# Water_Schematic2_1.net
KiCad netlist of a schematic drawn in EAGLE
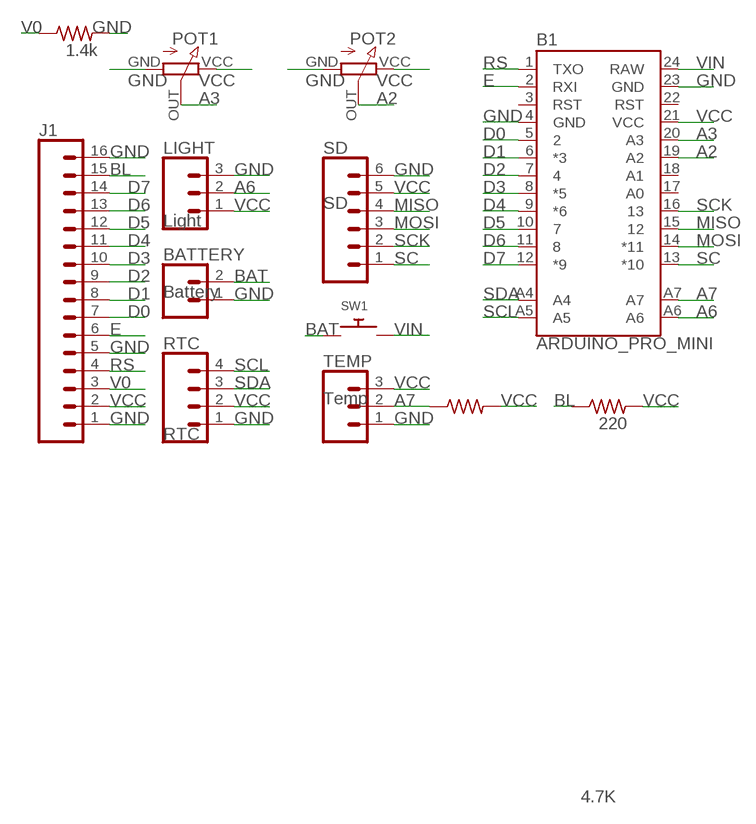
[diagram p0: schematic, sheet 1]

(export (version "E")
  (design (tool "Eeschema 10.0.6"))
  (components
    (comp (ref "B1")
      (value "ARDUINO_PRO_MINI")
      (footprint "eagle-import:ARDUINO_PRO_MINI")
      (libsource (lib "eagle-import") (part "ARDUINO_PRO_MINI"))
    )
    (comp (ref "BATTERY")
      (value "Battery")
      (footprint "eagle-import:MOLEX-1X2")
      (libsource (lib "eagle-import") (part "CONN_02POLAR"))
    )
    (comp (ref "J1")
      (value "CONN_16")
      (footprint "eagle-import:1X16")
      (libsource (lib "eagle-import") (part "CONN_16"))
    )
    (comp (ref "LIGHT")
      (value "Light")
      (footprint "eagle-import:1X03")
      (libsource (lib "eagle-import") (part "CONN_03"))
    )
    (comp (ref "POT1")
      (value "RM_065")
      (footprint "eagle-import:RM_065")
      (libsource (lib "eagle-import") (part "RM_065"))
    )
    (comp (ref "POT2")
      (value "RM_065")
      (footprint "eagle-import:RM_065")
      (libsource (lib "eagle-import") (part "RM_065"))
    )
    (comp (ref "R1")
      (value "4.7K")
      (footprint "eagle-import:0204_7")
      (libsource (lib "eagle-import") (part "R-US_0204/7"))
    )
    (comp (ref "R2")
      (value "220")
      (footprint "eagle-import:0204_7")
      (libsource (lib "eagle-import") (part "R-US_0204/7"))
    )
    (comp (ref "R3")
      (value "1.4k")
      (footprint "eagle-import:0204_7")
      (libsource (lib "eagle-import") (part "R-US_0204/7"))
    )
    (comp (ref "RTC")
      (value "RTC")
      (footprint "eagle-import:MOLEX-1X4")
      (libsource (lib "eagle-import") (part "CONN_04POLAR"))
    )
    (comp (ref "SD")
      (value "SD")
      (footprint "eagle-import:1X06")
      (libsource (lib "eagle-import") (part "CONN_06SILK_FEMALE_PTH"))
    )
    (comp (ref "SW1")
      (value "SWITCH_PUSHBUTTONEVQ-PE")
      (footprint "eagle-import:TACT_PANA-EVQ")
      (libsource (lib "eagle-import") (part "SWITCH_PUSHBUTTONEVQ-PE"))
    )
    (comp (ref "TEMP")
      (value "Temp")
      (footprint "eagle-import:1X03")
      (libsource (lib "eagle-import") (part "CONN_03"))
    )
  )
  (nets
    (net (code "1") (name "/A2") (class "Default")
      (node (ref "B1") (pin "19") (pinfunction "A2_19") (pintype "bidirectional"))
      (node (ref "POT2") (pin "OUT") (pinfunction "OUT_OUT") (pintype "passive"))
    )
    (net (code "2") (name "/A3") (class "Default")
      (node (ref "B1") (pin "20") (pinfunction "A3_20") (pintype "bidirectional"))
      (node (ref "POT1") (pin "OUT") (pinfunction "OUT_OUT") (pintype "passive"))
    )
    (net (code "3") (name "/A6") (class "Default")
      (node (ref "B1") (pin "A6") (pinfunction "A6_A6") (pintype "bidirectional"))
      (node (ref "LIGHT") (pin "2") (pinfunction "2_2") (pintype "passive"))
    )
    (net (code "4") (name "/A7") (class "Default")
      (node (ref "B1") (pin "A7") (pinfunction "A7_A7") (pintype "bidirectional"))
      (node (ref "R1") (pin "1") (pinfunction "1_1") (pintype "passive"))
      (node (ref "TEMP") (pin "2") (pinfunction "2_2") (pintype "passive"))
    )
    (net (code "5") (name "/BAT") (class "Default")
      (node (ref "BATTERY") (pin "2") (pinfunction "2_2") (pintype "passive"))
      (node (ref "SW1") (pin "P$1") (pinfunction "P$1_P$1") (pintype "passive"))
    )
    (net (code "6") (name "/BL") (class "Default")
      (node (ref "J1") (pin "15") (pinfunction "15_15") (pintype "passive"))
      (node (ref "R2") (pin "1") (pinfunction "1_1") (pintype "passive"))
    )
    (net (code "7") (name "/D0") (class "Default")
      (node (ref "B1") (pin "5") (pinfunction "2_5") (pintype "bidirectional"))
      (node (ref "J1") (pin "7") (pinfunction "7_7") (pintype "passive"))
    )
    (net (code "8") (name "/D1") (class "Default")
      (node (ref "B1") (pin "6") (pinfunction "*3_6") (pintype "bidirectional"))
      (node (ref "J1") (pin "8") (pinfunction "8_8") (pintype "passive"))
    )
    (net (code "9") (name "/D2") (class "Default")
      (node (ref "B1") (pin "7") (pinfunction "4_7") (pintype "bidirectional"))
      (node (ref "J1") (pin "9") (pinfunction "9_9") (pintype "passive"))
    )
    (net (code "10") (name "/D3") (class "Default")
      (node (ref "B1") (pin "8") (pinfunction "*5_8") (pintype "bidirectional"))
      (node (ref "J1") (pin "10") (pinfunction "10_10") (pintype "passive"))
    )
    (net (code "11") (name "/D4") (class "Default")
      (node (ref "B1") (pin "9") (pinfunction "*6_9") (pintype "bidirectional"))
      (node (ref "J1") (pin "11") (pinfunction "11_11") (pintype "passive"))
    )
    (net (code "12") (name "/D5") (class "Default")
      (node (ref "B1") (pin "10") (pinfunction "7_10") (pintype "bidirectional"))
      (node (ref "J1") (pin "12") (pinfunction "12_12") (pintype "passive"))
    )
    (net (code "13") (name "/D6") (class "Default")
      (node (ref "B1") (pin "11") (pinfunction "8_11") (pintype "bidirectional"))
      (node (ref "J1") (pin "13") (pinfunction "13_13") (pintype "passive"))
    )
    (net (code "14") (name "/D7") (class "Default")
      (node (ref "B1") (pin "12") (pinfunction "*9_12") (pintype "bidirectional"))
      (node (ref "J1") (pin "14") (pinfunction "14_14") (pintype "passive"))
    )
    (net (code "15") (name "/E") (class "Default")
      (node (ref "B1") (pin "2") (pinfunction "RXI_2") (pintype "bidirectional"))
      (node (ref "J1") (pin "6") (pinfunction "6_6") (pintype "passive"))
    )
    (net (code "16") (name "/GND") (class "Default")
      (node (ref "B1") (pin "23") (pinfunction "GND_23") (pintype "power_in"))
      (node (ref "B1") (pin "4") (pinfunction "GND_4") (pintype "power_in"))
      (node (ref "BATTERY") (pin "1") (pinfunction "1_1") (pintype "passive"))
      (node (ref "J1") (pin "1") (pinfunction "1_1") (pintype "passive"))
      (node (ref "J1") (pin "16") (pinfunction "16_16") (pintype "passive"))
      (node (ref "J1") (pin "5") (pinfunction "5_5") (pintype "passive"))
      (node (ref "LIGHT") (pin "3") (pinfunction "3_3") (pintype "passive"))
      (node (ref "POT1") (pin "GND") (pinfunction "GROUND_GND") (pintype "passive"))
      (node (ref "POT2") (pin "GND") (pinfunction "GROUND_GND") (pintype "passive"))
      (node (ref "R3") (pin "2") (pinfunction "2_2") (pintype "passive"))
      (node (ref "RTC") (pin "1") (pinfunction "1_1") (pintype "passive"))
      (node (ref "SD") (pin "6") (pinfunction "6_6") (pintype "passive"))
      (node (ref "TEMP") (pin "1") (pinfunction "1_1") (pintype "passive"))
    )
    (net (code "17") (name "/MISO") (class "Default")
      (node (ref "B1") (pin "15") (pinfunction "12_15") (pintype "bidirectional"))
      (node (ref "SD") (pin "4") (pinfunction "4_4") (pintype "passive"))
    )
    (net (code "18") (name "/MOSI") (class "Default")
      (node (ref "B1") (pin "14") (pinfunction "*11_14") (pintype "bidirectional"))
      (node (ref "SD") (pin "3") (pinfunction "3_3") (pintype "passive"))
    )
    (net (code "19") (name "/RS") (class "Default")
      (node (ref "B1") (pin "1") (pinfunction "TXO_1") (pintype "bidirectional"))
      (node (ref "J1") (pin "4") (pinfunction "4_4") (pintype "passive"))
    )
    (net (code "20") (name "/SC") (class "Default")
      (node (ref "B1") (pin "13") (pinfunction "*10_13") (pintype "bidirectional"))
      (node (ref "SD") (pin "1") (pinfunction "1_1") (pintype "passive"))
    )
    (net (code "21") (name "/SCK") (class "Default")
      (node (ref "B1") (pin "16") (pinfunction "13_16") (pintype "bidirectional"))
      (node (ref "SD") (pin "2") (pinfunction "2_2") (pintype "passive"))
    )
    (net (code "22") (name "/SCL") (class "Default")
      (node (ref "B1") (pin "A5") (pinfunction "A5_A5") (pintype "bidirectional"))
      (node (ref "RTC") (pin "4") (pinfunction "4_4") (pintype "passive"))
    )
    (net (code "23") (name "/SDA") (class "Default")
      (node (ref "B1") (pin "A4") (pinfunction "A4_A4") (pintype "bidirectional"))
      (node (ref "RTC") (pin "3") (pinfunction "3_3") (pintype "passive"))
    )
    (net (code "24") (name "/V0") (class "Default")
      (node (ref "J1") (pin "3") (pinfunction "3_3") (pintype "passive"))
      (node (ref "R3") (pin "1") (pinfunction "1_1") (pintype "passive"))
    )
    (net (code "25") (name "/VCC") (class "Default")
      (node (ref "B1") (pin "21") (pinfunction "VCC_21") (pintype "power_in"))
      (node (ref "J1") (pin "2") (pinfunction "2_2") (pintype "passive"))
      (node (ref "LIGHT") (pin "1") (pinfunction "1_1") (pintype "passive"))
      (node (ref "POT1") (pin "VCC") (pinfunction "VCC_VCC") (pintype "passive"))
      (node (ref "POT2") (pin "VCC") (pinfunction "VCC_VCC") (pintype "passive"))
      (node (ref "R1") (pin "2") (pinfunction "2_2") (pintype "passive"))
      (node (ref "R2") (pin "2") (pinfunction "2_2") (pintype "passive"))
      (node (ref "RTC") (pin "2") (pinfunction "2_2") (pintype "passive"))
      (node (ref "SD") (pin "5") (pinfunction "5_5") (pintype "passive"))
      (node (ref "TEMP") (pin "3") (pinfunction "3_3") (pintype "passive"))
    )
    (net (code "26") (name "/VIN") (class "Default")
      (node (ref "B1") (pin "24") (pinfunction "RAW_24") (pintype "power_in"))
      (node (ref "SW1") (pin "P$2") (pinfunction "P$2_P$2") (pintype "passive"))
    )
    (net (code "27") (name "unconnected-(B1-A0-Pad17)") (class "Default")
      (node (ref "B1") (pin "17") (pinfunction "A0_17") (pintype "bidirectional"))
    )
    (net (code "28") (name "unconnected-(B1-A1-Pad18)") (class "Default")
      (node (ref "B1") (pin "18") (pinfunction "A1_18") (pintype "bidirectional"))
    )
    (net (code "29") (name "unconnected-(B1-RST-Pad3)") (class "Default")
      (node (ref "B1") (pin "3") (pinfunction "RST_3") (pintype "bidirectional"))
    )
    (net (code "30") (name "unconnected-(B1-RST-Pad22)") (class "Default")
      (node (ref "B1") (pin "22") (pinfunction "RST_22") (pintype "bidirectional"))
    )
  )
)
